# SH4_-_SD_CARD.net
KiCad netlist of a schematic drawn in Altium Designer
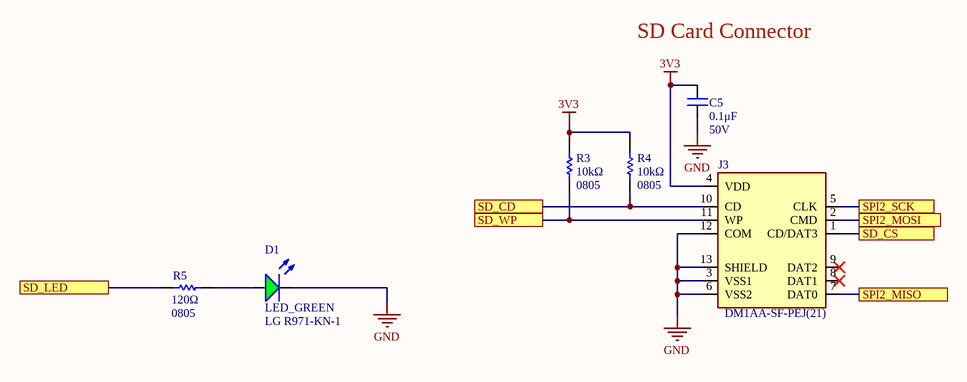
[diagram p0: SH4 - SD CARD.SchDoc]

(export (version "E")
  (design (tool "Eeschema 10.0.6"))
  (components
    (comp (ref "C5")
      (value "0.1μF")
      (footprint "CAP2012")
      (description "CAP CER 0.1UF 50V X7R 0805")
      (fields
        (field (name "VOLTAGE RATING") "50V")
        (field (name "LCSC PART #") "C49678")
        (field (name "Comment") "CAP_0.1uF_50V_0805")
      )
      (libsource (lib "UWRT_Schematic_Library_2020") (part "CAP_0.1uF_50V_0805"))
    )
    (comp (ref "D1")
      (value "LED_GREEN")
      (footprint "LED_0805_GREEN")
      (description "LED GREEN DIFFUSED 0805 SMD")
      (fields (field (name "MANUFACTURER PART NUMBER 1") "LG R971-KN-1"))
      (libsource (lib "UWRT_Schematic_Library_2020") (part "LED_GREEN"))
    )
    (comp (ref "J3")
      (value "CON_SD_CARD")
      (footprint "HRS_DM1AA-SF-PEJ(21)")
      (description "CONN SD CARD PUSH-PUSH R/A SMD")
      (fields (field (name "MANUFACTURER PART NUMBER 1") "DM1AA-SF-PEJ(21)"))
      (libsource (lib "UWRT_Schematic_Library_2020") (part "CON_SD_CARD"))
    )
    (comp (ref "R3")
      (value "10kΩ")
      (footprint "RES0805")
      (description "RES 10K OHM 5% 1/8W 0805")
      (fields
        (field (name "PACKAGE/FOOTPRINT") "0805")
        (field (name "LCSC PART #") "C17414")
        (field (name "Comment") "RES_10kΩ_0805_5%")
      )
      (libsource (lib "UWRT_Schematic_Library_2020") (part "RES_10kΩ_0805_5%"))
    )
    (comp (ref "R4")
      (value "10kΩ")
      (footprint "RES0805")
      (description "RES 10K OHM 5% 1/8W 0805")
      (fields
        (field (name "PACKAGE/FOOTPRINT") "0805")
        (field (name "LCSC PART #") "C17414")
        (field (name "Comment") "RES_10kΩ_0805_5%")
      )
      (libsource (lib "UWRT_Schematic_Library_2020") (part "RES_10kΩ_0805_5%"))
    )
    (comp (ref "R5")
      (value "120Ω")
      (footprint "RESC0805")
      (description "RES 120 OHM 1% 1/8W 0805")
      (fields
        (field (name "LCSC PART #") "C17437")
        (field (name "PACKAGE/FOOTPRINT") "0805")
        (field (name "Comment") "RES_120Ω_0805_1%")
      )
      (libsource (lib "UWRT_Schematic_Library_2020") (part "RES_120Ω_0805_1%"))
    )
  )
  (nets
    (net (code "1") (name "/SD_CD") (class "Default")
      (node (ref "J3") (pin "10") (pinfunction "CD_10") (pintype "passive"))
      (node (ref "R4") (pin "1") (pinfunction "1_1") (pintype "passive"))
    )
    (net (code "2") (name "/SD_CS") (class "Default")
      (node (ref "J3") (pin "1") (pinfunction "CD/DAT3_1") (pintype "passive"))
    )
    (net (code "3") (name "/SD_LED") (class "Default")
      (node (ref "R5") (pin "1") (pinfunction "1_1") (pintype "passive"))
    )
    (net (code "4") (name "/SD_WP") (class "Default")
      (node (ref "J3") (pin "11") (pinfunction "WP_11") (pintype "passive"))
      (node (ref "R3") (pin "1") (pinfunction "1_1") (pintype "passive"))
    )
    (net (code "5") (name "/SPI2_MISO") (class "Default")
      (node (ref "J3") (pin "7") (pinfunction "DAT0_7") (pintype "passive"))
    )
    (net (code "6") (name "/SPI2_MOSI") (class "Default")
      (node (ref "J3") (pin "2") (pinfunction "CMD_2") (pintype "passive"))
    )
    (net (code "7") (name "/SPI2_SCK") (class "Default")
      (node (ref "J3") (pin "5") (pinfunction "CLK_5") (pintype "passive"))
    )
    (net (code "8") (name "3V3") (class "Default")
      (node (ref "C5") (pin "2") (pinfunction "2_2") (pintype "passive"))
      (node (ref "J3") (pin "4") (pinfunction "VDD_4") (pintype "power_in"))
      (node (ref "R3") (pin "2") (pinfunction "2_2") (pintype "passive"))
      (node (ref "R4") (pin "2") (pinfunction "2_2") (pintype "passive"))
    )
    (net (code "9") (name "GND") (class "Default")
      (node (ref "C5") (pin "1") (pinfunction "1_1") (pintype "passive"))
      (node (ref "D1") (pin "2") (pinfunction "K_2") (pintype "passive"))
      (node (ref "J3") (pin "12") (pinfunction "COM_12") (pintype "passive"))
      (node (ref "J3") (pin "13") (pinfunction "SHIELD_13") (pintype "passive"))
      (node (ref "J3") (pin "3") (pinfunction "VSS1_3") (pintype "power_in"))
      (node (ref "J3") (pin "6") (pinfunction "VSS2_6") (pintype "power_in"))
    )
    (net (code "10") (name "Net-(D1-A)") (class "Default")
      (node (ref "D1") (pin "1") (pinfunction "A_1") (pintype "passive"))
      (node (ref "R5") (pin "2") (pinfunction "2_2") (pintype "passive"))
    )
    (net (code "11") (name "unconnected-(J3-DAT1-Pad8)") (class "Default")
      (node (ref "J3") (pin "8") (pinfunction "DAT1_8") (pintype "passive+no_connect"))
    )
    (net (code "12") (name "unconnected-(J3-DAT2-Pad9)") (class "Default")
      (node (ref "J3") (pin "9") (pinfunction "DAT2_9") (pintype "passive+no_connect"))
    )
  )
)
